# esp32_radio_sch.net
KiCad netlist of a schematic drawn in Altium Designer
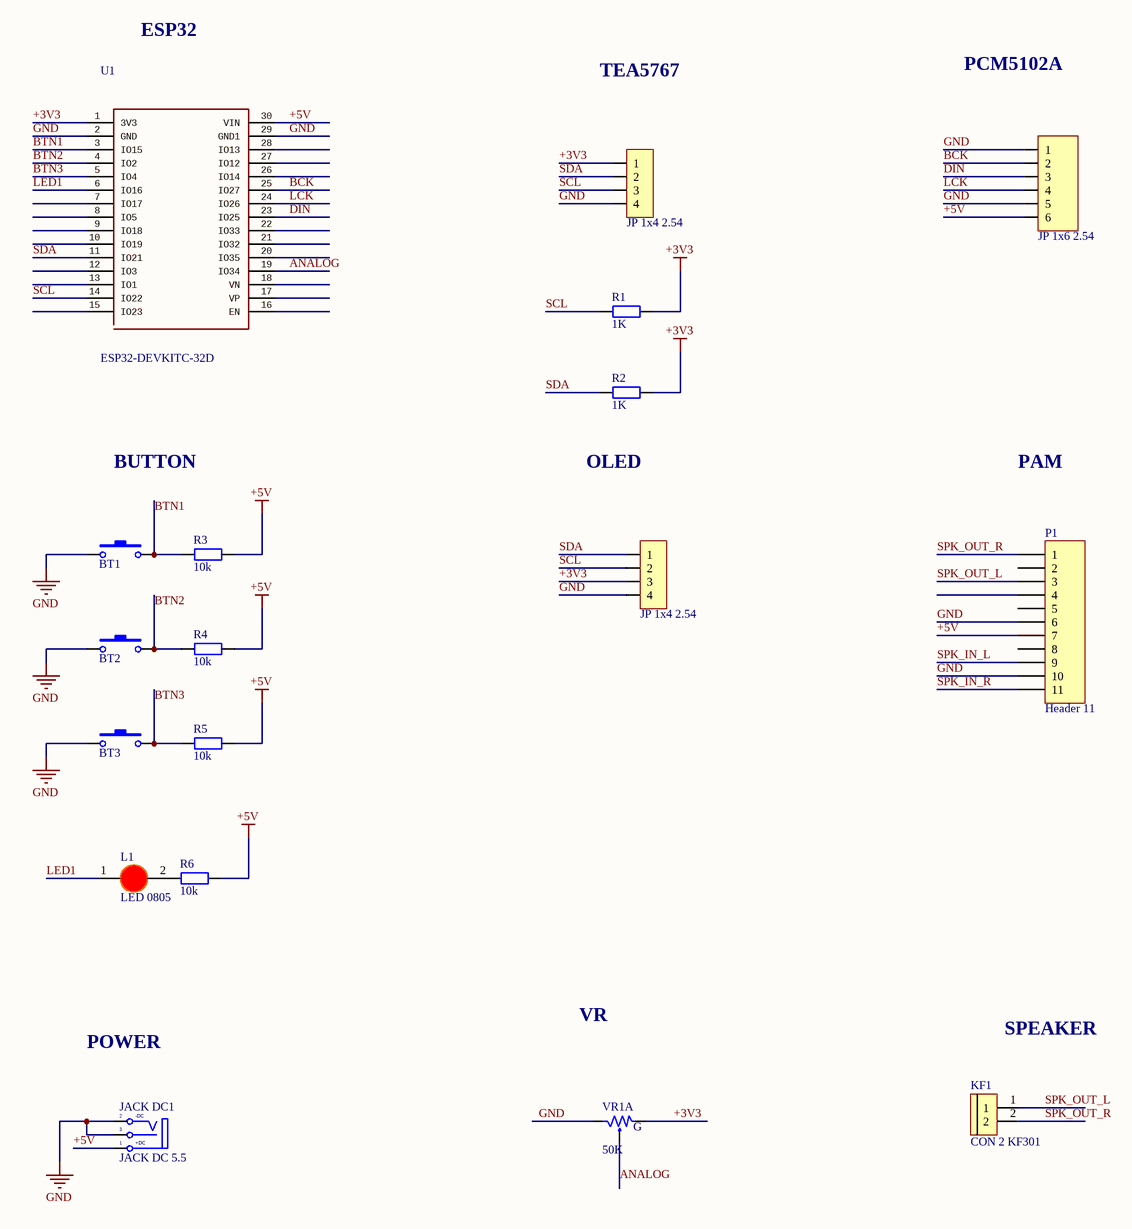
[diagram p0: esp32_radio_sch.SchDoc]

(export (version "E")
  (design (tool "Eeschema 10.0.6"))
  (components
    (comp (ref "BT1")
      (value "Nut Nhan 2 Chan SMD 3x6x2.5")
      (footprint "Nut Nhan 2 Chan SMD 3x6x2.5")
      (libsource (lib "Altium_Lib_by_KhueNguyenCreator") (part "Nut Nhan 2 Chan SMD 3x6x2.5"))
    )
    (comp (ref "BT2")
      (value "Nut Nhan 2 Chan SMD 3x6x2.5")
      (footprint "Nut Nhan 2 Chan SMD 3x6x2.5")
      (libsource (lib "Altium_Lib_by_KhueNguyenCreator") (part "Nut Nhan 2 Chan SMD 3x6x2.5"))
    )
    (comp (ref "BT3")
      (value "Nut Nhan 2 Chan SMD 3x6x2.5")
      (footprint "Nut Nhan 2 Chan SMD 3x6x2.5")
      (libsource (lib "Altium_Lib_by_KhueNguyenCreator") (part "Nut Nhan 2 Chan SMD 3x6x2.5"))
    )
    (comp (ref "JACK DC1")
      (value "JACK DC 5.5")
      (footprint "JACK DC 5.5")
      (libsource (lib "Altium_Lib_by_KhueNguyenCreator") (part "JACK DC 5.5"))
    )
    (comp (ref "JP1")
      (value "JP 1x6 2.54")
      (footprint "JP 1x6 CT")
      (description "Cắm")
      (libsource (lib "Altium_Lib_by_KhueNguyenCreator") (part "JP 1x6 2.54 Cai Thang"))
    )
    (comp (ref "JP2")
      (value "JP 1x4 2.54")
      (footprint "JP 1x4 CC")
      (description "Cắm")
      (libsource (lib "Altium_Lib_by_KhueNguyenCreator") (part "JP 1x4 2.54 Cai Cong"))
    )
    (comp (ref "JP3")
      (value "JP 1x4 2.54")
      (footprint "JP 1x4 CT")
      (description "Cắm")
      (libsource (lib "Altium_Lib_by_KhueNguyenCreator") (part "JP 1x4 2.54 Cai Thang"))
    )
    (comp (ref "KF1")
      (value "CON 2 KF301")
      (footprint "Con 2 KF301 5.08")
      (description "Cắm")
      (libsource (lib "Altium_Lib_by_KhueNguyenCreator") (part "CON 2 KF301"))
    )
    (comp (ref "L1")
      (value "LED 0805")
      (footprint "LED-0805-Red")
      (description "Dán")
      (libsource (lib "Altium_Lib_by_KhueNguyenCreator") (part "LED 0805 Do"))
    )
    (comp (ref "P1")
      (value "Header 11")
      (footprint "HDR1X11")
      (description "Header, 11-Pin")
      (fields (field (name "PUBLISHER") "Altium Limited"))
      (libsource (lib "Miscellaneous Connectors") (part "Header 11"))
    )
    (comp (ref "R1")
      (value "1K")
      (footprint "tro smd 0805")
      (description "Dán")
      (libsource (lib "Altium_Lib_by_KhueNguyenCreator") (part "Tro 0805 1% 1k"))
    )
    (comp (ref "R2")
      (value "1K")
      (footprint "tro smd 0805")
      (description "Dán")
      (libsource (lib "Altium_Lib_by_KhueNguyenCreator") (part "Tro 0805 1% 1k"))
    )
    (comp (ref "R3")
      (value "10k")
      (footprint "tro smd 0805")
      (description "Dán")
      (libsource (lib "Altium_Lib_by_KhueNguyenCreator") (part "Tro 0805 1% 1k"))
    )
    (comp (ref "R4")
      (value "10k")
      (footprint "tro smd 0805")
      (description "Dán")
      (libsource (lib "Altium_Lib_by_KhueNguyenCreator") (part "Tro 0805 1% 1k"))
    )
    (comp (ref "R5")
      (value "10k")
      (footprint "tro smd 0805")
      (description "Dán")
      (libsource (lib "Altium_Lib_by_KhueNguyenCreator") (part "Tro 0805 1% 1k"))
    )
    (comp (ref "R6")
      (value "10k")
      (footprint "tro smd 0805")
      (description "Dán")
      (libsource (lib "Altium_Lib_by_KhueNguyenCreator") (part "Tro 0805 1% 1k"))
    )
    (comp (ref "U1")
      (value "ESP32-DEVKITC-32D")
      (footprint "MODULE_ESP32-DEVKITV1")
      (description "Eval Board For Esp-Wroom-32")
      (fields (field (name "MF") "Espressif Systems"))
      (libsource (lib "AltiumLibraryDDT") (part "ESP32-DEVKITC-32D"))
    )
    (comp (ref "VR1")
      (value "50K")
      (footprint "VR-D1")
      (description "Volume control Dual")
      (libsource (lib "LIBRARY1") (part "VR-DP"))
    )
  )
  (nets
    (net (code "1") (name "+3V3") (class "Default")
      (node (ref "JP2") (pin "1") (pinfunction "1_1") (pintype "passive"))
      (node (ref "JP3") (pin "3") (pinfunction "3_3") (pintype "passive"))
      (node (ref "R1") (pin "2") (pinfunction "2_2") (pintype "passive"))
      (node (ref "R2") (pin "2") (pinfunction "2_2") (pintype "passive"))
      (node (ref "U1") (pin "1") (pinfunction "3V3_1") (pintype "passive"))
      (node (ref "VR1") (pin "1") (pinfunction "1_1") (pintype "passive"))
    )
    (net (code "2") (name "+5V") (class "Default")
      (node (ref "JACK DC1") (pin "1") (pinfunction "T_1") (pintype "passive"))
      (node (ref "JP1") (pin "6") (pinfunction "6_6") (pintype "passive"))
      (node (ref "P1") (pin "7") (pinfunction "7_7") (pintype "passive"))
      (node (ref "R3") (pin "2") (pinfunction "2_2") (pintype "passive"))
      (node (ref "R4") (pin "2") (pinfunction "2_2") (pintype "passive"))
      (node (ref "R5") (pin "2") (pinfunction "2_2") (pintype "passive"))
      (node (ref "R6") (pin "2") (pinfunction "2_2") (pintype "passive"))
      (node (ref "U1") (pin "30") (pinfunction "VIN_30") (pintype "passive"))
    )
    (net (code "3") (name "/ANALOG") (class "Default")
      (node (ref "U1") (pin "19") (pinfunction "IO34_19") (pintype "passive"))
      (node (ref "VR1") (pin "2") (pinfunction "2_2") (pintype "passive"))
    )
    (net (code "4") (name "/BCK") (class "Default")
      (node (ref "JP1") (pin "2") (pinfunction "2_2") (pintype "passive"))
      (node (ref "U1") (pin "25") (pinfunction "IO27_25") (pintype "passive"))
    )
    (net (code "5") (name "/BTN1") (class "Default")
      (node (ref "BT1") (pin "2") (pinfunction "2_2") (pintype "passive"))
      (node (ref "R3") (pin "1") (pinfunction "1_1") (pintype "passive"))
      (node (ref "U1") (pin "3") (pinfunction "IO15_3") (pintype "passive"))
    )
    (net (code "6") (name "/BTN2") (class "Default")
      (node (ref "BT2") (pin "2") (pinfunction "2_2") (pintype "passive"))
      (node (ref "R4") (pin "1") (pinfunction "1_1") (pintype "passive"))
      (node (ref "U1") (pin "4") (pinfunction "IO2_4") (pintype "passive"))
    )
    (net (code "7") (name "/BTN3") (class "Default")
      (node (ref "BT3") (pin "2") (pinfunction "2_2") (pintype "passive"))
      (node (ref "R5") (pin "1") (pinfunction "1_1") (pintype "passive"))
      (node (ref "U1") (pin "5") (pinfunction "IO4_5") (pintype "passive"))
    )
    (net (code "8") (name "/DIN") (class "Default")
      (node (ref "JP1") (pin "3") (pinfunction "3_3") (pintype "passive"))
      (node (ref "U1") (pin "23") (pinfunction "IO25_23") (pintype "passive"))
    )
    (net (code "9") (name "/LCK") (class "Default")
      (node (ref "JP1") (pin "4") (pinfunction "4_4") (pintype "passive"))
      (node (ref "U1") (pin "24") (pinfunction "IO26_24") (pintype "passive"))
    )
    (net (code "10") (name "/LED1") (class "Default")
      (node (ref "L1") (pin "1") (pinfunction "A_1") (pintype "passive"))
      (node (ref "U1") (pin "6") (pinfunction "IO16_6") (pintype "passive"))
    )
    (net (code "11") (name "/SCL") (class "Default")
      (node (ref "JP2") (pin "3") (pinfunction "3_3") (pintype "passive"))
      (node (ref "JP3") (pin "2") (pinfunction "2_2") (pintype "passive"))
      (node (ref "R1") (pin "1") (pinfunction "1_1") (pintype "passive"))
      (node (ref "U1") (pin "14") (pinfunction "IO22_14") (pintype "passive"))
    )
    (net (code "12") (name "/SDA") (class "Default")
      (node (ref "JP2") (pin "2") (pinfunction "2_2") (pintype "passive"))
      (node (ref "JP3") (pin "1") (pinfunction "1_1") (pintype "passive"))
      (node (ref "R2") (pin "1") (pinfunction "1_1") (pintype "passive"))
      (node (ref "U1") (pin "11") (pinfunction "IO21_11") (pintype "passive"))
    )
    (net (code "13") (name "/SPK_IN_L") (class "Default")
      (node (ref "P1") (pin "9") (pinfunction "9_9") (pintype "passive"))
    )
    (net (code "14") (name "/SPK_IN_R") (class "Default")
      (node (ref "P1") (pin "11") (pinfunction "11_11") (pintype "passive"))
    )
    (net (code "15") (name "/SPK_OUT_L") (class "Default")
      (node (ref "KF1") (pin "1") (pinfunction "1_1") (pintype "passive"))
      (node (ref "P1") (pin "3") (pinfunction "3_3") (pintype "passive"))
    )
    (net (code "16") (name "/SPK_OUT_R") (class "Default")
      (node (ref "KF1") (pin "2") (pinfunction "2_2") (pintype "passive"))
      (node (ref "P1") (pin "1") (pinfunction "1_1") (pintype "passive"))
    )
    (net (code "17") (name "GND") (class "Default")
      (node (ref "BT1") (pin "1") (pinfunction "1_1") (pintype "passive"))
      (node (ref "BT2") (pin "1") (pinfunction "1_1") (pintype "passive"))
      (node (ref "BT3") (pin "1") (pinfunction "1_1") (pintype "passive"))
      (node (ref "JACK DC1") (pin "2") (pinfunction "TN_2") (pintype "passive"))
      (node (ref "JACK DC1") (pin "3") (pinfunction "S_3") (pintype "power_in"))
      (node (ref "JP1") (pin "1") (pinfunction "1_1") (pintype "passive"))
      (node (ref "JP1") (pin "5") (pinfunction "5_5") (pintype "passive"))
      (node (ref "JP2") (pin "4") (pinfunction "4_4") (pintype "passive"))
      (node (ref "JP3") (pin "4") (pinfunction "4_4") (pintype "passive"))
      (node (ref "P1") (pin "10") (pinfunction "10_10") (pintype "passive"))
      (node (ref "P1") (pin "6") (pinfunction "6_6") (pintype "passive"))
      (node (ref "U1") (pin "2") (pinfunction "GND_2") (pintype "passive"))
      (node (ref "U1") (pin "29") (pinfunction "GND1_29") (pintype "passive"))
      (node (ref "VR1") (pin "3") (pinfunction "3_3") (pintype "passive"))
    )
    (net (code "18") (name "Net-(L1-K)") (class "Default")
      (node (ref "L1") (pin "2") (pinfunction "K_2") (pintype "passive"))
      (node (ref "R6") (pin "1") (pinfunction "1_1") (pintype "passive"))
    )
    (net (code "19") (name "unconnected-(P1-Pad2)") (class "Default")
      (node (ref "P1") (pin "2") (pinfunction "2_2") (pintype "passive"))
    )
    (net (code "20") (name "unconnected-(P1-Pad4)") (class "Default")
      (node (ref "P1") (pin "4") (pinfunction "4_4") (pintype "passive"))
    )
    (net (code "21") (name "unconnected-(P1-Pad5)") (class "Default")
      (node (ref "P1") (pin "5") (pinfunction "5_5") (pintype "passive"))
    )
    (net (code "22") (name "unconnected-(P1-Pad8)") (class "Default")
      (node (ref "P1") (pin "8") (pinfunction "8_8") (pintype "passive"))
    )
    (net (code "23") (name "unconnected-(U1-EN-Pad16)") (class "Default")
      (node (ref "U1") (pin "16") (pinfunction "EN_16") (pintype "passive"))
    )
    (net (code "24") (name "unconnected-(U1-IO1-Pad13)") (class "Default")
      (node (ref "U1") (pin "13") (pinfunction "IO1_13") (pintype "passive"))
    )
    (net (code "25") (name "unconnected-(U1-IO3-Pad12)") (class "Default")
      (node (ref "U1") (pin "12") (pinfunction "IO3_12") (pintype "passive"))
    )
    (net (code "26") (name "unconnected-(U1-IO5-Pad8)") (class "Default")
      (node (ref "U1") (pin "8") (pinfunction "IO5_8") (pintype "passive"))
    )
    (net (code "27") (name "unconnected-(U1-IO12-Pad27)") (class "Default")
      (node (ref "U1") (pin "27") (pinfunction "IO12_27") (pintype "passive"))
    )
    (net (code "28") (name "unconnected-(U1-IO13-Pad28)") (class "Default")
      (node (ref "U1") (pin "28") (pinfunction "IO13_28") (pintype "passive"))
    )
    (net (code "29") (name "unconnected-(U1-IO14-Pad26)") (class "Default")
      (node (ref "U1") (pin "26") (pinfunction "IO14_26") (pintype "passive"))
    )
    (net (code "30") (name "unconnected-(U1-IO17-Pad7)") (class "Default")
      (node (ref "U1") (pin "7") (pinfunction "IO17_7") (pintype "passive"))
    )
    (net (code "31") (name "unconnected-(U1-IO18-Pad9)") (class "Default")
      (node (ref "U1") (pin "9") (pinfunction "IO18_9") (pintype "passive"))
    )
    (net (code "32") (name "unconnected-(U1-IO19-Pad10)") (class "Default")
      (node (ref "U1") (pin "10") (pinfunction "IO19_10") (pintype "passive"))
    )
    (net (code "33") (name "unconnected-(U1-IO23-Pad15)") (class "Default")
      (node (ref "U1") (pin "15") (pinfunction "IO23_15") (pintype "passive"))
    )
    (net (code "34") (name "unconnected-(U1-IO32-Pad21)") (class "Default")
      (node (ref "U1") (pin "21") (pinfunction "IO32_21") (pintype "passive"))
    )
    (net (code "35") (name "unconnected-(U1-IO33-Pad22)") (class "Default")
      (node (ref "U1") (pin "22") (pinfunction "IO33_22") (pintype "passive"))
    )
    (net (code "36") (name "unconnected-(U1-IO35-Pad20)") (class "Default")
      (node (ref "U1") (pin "20") (pinfunction "IO35_20") (pintype "passive"))
    )
    (net (code "37") (name "unconnected-(U1-VN-Pad18)") (class "Default")
      (node (ref "U1") (pin "18") (pinfunction "VN_18") (pintype "passive"))
    )
    (net (code "38") (name "unconnected-(U1-VP-Pad17)") (class "Default")
      (node (ref "U1") (pin "17") (pinfunction "VP_17") (pintype "passive"))
    )
  )
)
